# circuito1.net
KiCad netlist of a schematic drawn in Altium Designer
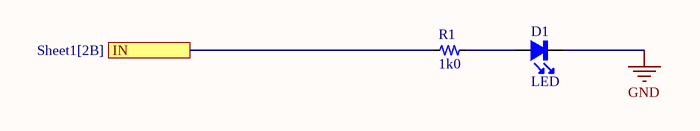
[diagram p0: circuito1.SchDoc]

(export (version "E")
  (design (tool "Eeschema 10.0.6"))
  (components
    (comp (ref "D1")
      (value "LED")
      (footprint "LED-0805")
      (description "LED - Light-Emitting Diode")
      (libsource (lib "RasUNMSM") (part "LED"))
    )
    (comp (ref "R1")
      (value "1k0")
      (footprint "R2512")
      (description "Single resistor")
      (fields (field (name "POWER") "0.125W"))
      (libsource (lib "RasUNMSM") (part "Resistor"))
    )
  )
  (nets
    (net (code "1") (name "/IN") (class "Default")
      (node (ref "R1") (pin "1") (pinfunction "1_1") (pintype "passive"))
    )
    (net (code "2") (name "GND") (class "Default")
      (node (ref "D1") (pin "1") (pinfunction "1_1") (pintype "passive"))
    )
    (net (code "3") (name "Net-(D1-Pad2)") (class "Default")
      (node (ref "D1") (pin "2") (pinfunction "2_2") (pintype "passive"))
      (node (ref "R1") (pin "2") (pinfunction "2_2") (pintype "passive"))
    )
  )
)
